# stepper_x2.net
KiCad netlist of a schematic drawn in EAGLE
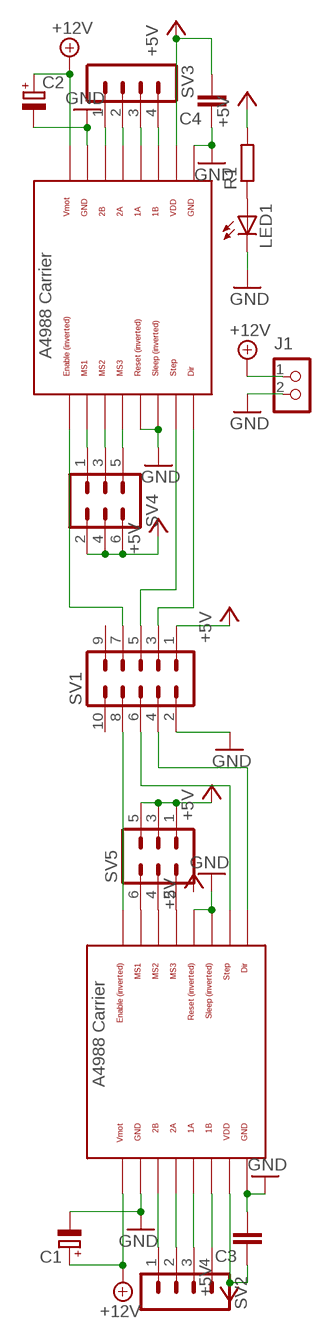
[diagram p0: schematic, sheet 1]

(export (version "E")
  (design (tool "Eeschema 10.0.6"))
  (components
    (comp (ref "C1")
      (value "CPOL-EU153CLV-0605")
      (footprint "eagle-import:153CLV-0605")
      (libsource (lib "eagle-import") (part "CPOL-EU153CLV-0605"))
    )
    (comp (ref "C2")
      (value "CPOL-EU153CLV-0605")
      (footprint "eagle-import:153CLV-0605")
      (libsource (lib "eagle-import") (part "CPOL-EU153CLV-0605"))
    )
    (comp (ref "C3")
      (value "C-EU025-030X050")
      (footprint "eagle-import:C025-030X050")
      (libsource (lib "eagle-import") (part "C-EU025-030X050"))
    )
    (comp (ref "C4")
      (value "C-EU025-030X050")
      (footprint "eagle-import:C025-030X050")
      (libsource (lib "eagle-import") (part "C-EU025-030X050"))
    )
    (comp (ref "J1")
      (value "CON_TERMINAL_BLOCK_02-5MM")
      (footprint "eagle-import:TERMINAL_BLOCK_2P_5")
      (libsource (lib "eagle-import") (part "CON_TERMINAL_BLOCK_02-5MM"))
    )
    (comp (ref "LED1")
      (value "LED5MM")
      (footprint "eagle-import:LED5MM")
      (libsource (lib "eagle-import") (part "LED5MM"))
    )
    (comp (ref "R1")
      (value "R-EU_0411/12")
      (footprint "eagle-import:0411_12")
      (libsource (lib "eagle-import") (part "R-EU_0411/12"))
    )
    (comp (ref "SV1")
      (value "MA05-2")
      (footprint "eagle-import:MA05-2")
      (libsource (lib "eagle-import") (part "MA05-2"))
    )
    (comp (ref "SV2")
      (value "MA04-1")
      (footprint "eagle-import:MA04-1")
      (libsource (lib "eagle-import") (part "MA04-1"))
    )
    (comp (ref "SV3")
      (value "MA04-1")
      (footprint "eagle-import:MA04-1")
      (libsource (lib "eagle-import") (part "MA04-1"))
    )
    (comp (ref "SV4")
      (value "MA03-2")
      (footprint "eagle-import:MA03-2")
      (libsource (lib "eagle-import") (part "MA03-2"))
    )
    (comp (ref "SV5")
      (value "MA03-2")
      (footprint "eagle-import:MA03-2")
      (libsource (lib "eagle-import") (part "MA03-2"))
    )
    (comp (ref "U$1")
      (value "POLOLU_A4983CARRIER")
      (footprint "eagle-import:A4988BREAKOUT")
      (libsource (lib "eagle-import") (part "POLOLU_A4983CARRIER"))
    )
    (comp (ref "U$2")
      (value "POLOLU_A4983CARRIER")
      (footprint "eagle-import:A4988BREAKOUT")
      (libsource (lib "eagle-import") (part "POLOLU_A4983CARRIER"))
    )
  )
  (nets
    (net (code "1") (name "+5V") (class "Default")
      (node (ref "C3") (pin "1") (pinfunction "1_1") (pintype "passive"))
      (node (ref "C4") (pin "2") (pinfunction "2_2") (pintype "passive"))
      (node (ref "R1") (pin "2") (pinfunction "2_2") (pintype "passive"))
      (node (ref "SV1") (pin "1") (pinfunction "1_1") (pintype "passive"))
      (node (ref "SV4") (pin "2") (pinfunction "2_2") (pintype "passive"))
      (node (ref "SV4") (pin "4") (pinfunction "4_4") (pintype "passive"))
      (node (ref "SV4") (pin "6") (pinfunction "6_6") (pintype "passive"))
      (node (ref "SV5") (pin "1") (pinfunction "1_1") (pintype "passive"))
      (node (ref "SV5") (pin "3") (pinfunction "3_3") (pintype "passive"))
      (node (ref "SV5") (pin "5") (pinfunction "5_5") (pintype "passive"))
      (node (ref "U$1") (pin "VDD") (pinfunction "VDD_VDD") (pintype "power_in"))
      (node (ref "U$2") (pin "VDD") (pinfunction "VDD_VDD") (pintype "power_in"))
    )
    (net (code "2") (name "+12V") (class "Default")
      (node (ref "C1") (pin "+") (pinfunction "+_+") (pintype "passive"))
      (node (ref "C2") (pin "+") (pinfunction "+_+") (pintype "passive"))
      (node (ref "J1") (pin "1") (pinfunction "1_1") (pintype "passive"))
      (node (ref "U$1") (pin "VMOT") (pinfunction "VMOT_VMOT") (pintype "power_in"))
      (node (ref "U$2") (pin "VMOT") (pinfunction "VMOT_VMOT") (pintype "power_in"))
    )
    (net (code "3") (name "GND") (class "Default")
      (node (ref "C1") (pin "-") (pinfunction "-_-") (pintype "passive"))
      (node (ref "C2") (pin "-") (pinfunction "-_-") (pintype "passive"))
      (node (ref "C3") (pin "2") (pinfunction "2_2") (pintype "passive"))
      (node (ref "C4") (pin "1") (pinfunction "1_1") (pintype "passive"))
      (node (ref "J1") (pin "2") (pinfunction "2_2") (pintype "passive"))
      (node (ref "LED1") (pin "K") (pinfunction "C_K") (pintype "passive"))
      (node (ref "SV1") (pin "2") (pinfunction "2_2") (pintype "passive"))
      (node (ref "U$1") (pin "GND") (pinfunction "GND_GND") (pintype "power_in"))
      (node (ref "U$1") (pin "GND@0") (pinfunction "GND_GND@0") (pintype "power_in"))
      (node (ref "U$1") (pin "RST") (pinfunction "RST_RST") (pintype "input"))
      (node (ref "U$1") (pin "SLP") (pinfunction "SLEEP_SLP") (pintype "input"))
      (node (ref "U$2") (pin "GND") (pinfunction "GND_GND") (pintype "power_in"))
      (node (ref "U$2") (pin "GND@0") (pinfunction "GND_GND@0") (pintype "power_in"))
      (node (ref "U$2") (pin "RST") (pinfunction "RST_RST") (pintype "input"))
      (node (ref "U$2") (pin "SLP") (pinfunction "SLEEP_SLP") (pintype "input"))
    )
    (net (code "4") (name "Net-(LED1-PadA)") (class "Default")
      (node (ref "LED1") (pin "A") (pinfunction "A_A") (pintype "passive"))
      (node (ref "R1") (pin "1") (pinfunction "1_1") (pintype "passive"))
    )
    (net (code "5") (name "Net-(SV1-Pad3)") (class "Default")
      (node (ref "SV1") (pin "3") (pinfunction "3_3") (pintype "passive"))
      (node (ref "U$1") (pin "DIR") (pinfunction "DIR_DIR") (pintype "input"))
    )
    (net (code "6") (name "Net-(SV1-Pad4)") (class "Default")
      (node (ref "SV1") (pin "4") (pinfunction "4_4") (pintype "passive"))
      (node (ref "U$2") (pin "DIR") (pinfunction "DIR_DIR") (pintype "input"))
    )
    (net (code "7") (name "Net-(SV1-Pad5)") (class "Default")
      (node (ref "SV1") (pin "5") (pinfunction "5_5") (pintype "passive"))
      (node (ref "U$1") (pin "STEP") (pinfunction "STEP_STEP") (pintype "input"))
    )
    (net (code "8") (name "Net-(SV1-Pad6)") (class "Default")
      (node (ref "SV1") (pin "6") (pinfunction "6_6") (pintype "passive"))
      (node (ref "U$2") (pin "STEP") (pinfunction "STEP_STEP") (pintype "input"))
    )
    (net (code "9") (name "Net-(SV1-Pad7)") (class "Default")
      (node (ref "SV1") (pin "7") (pinfunction "7_7") (pintype "passive"))
      (node (ref "U$1") (pin "EN") (pinfunction "EN_EN") (pintype "input"))
    )
    (net (code "10") (name "Net-(SV1-Pad8)") (class "Default")
      (node (ref "SV1") (pin "8") (pinfunction "8_8") (pintype "passive"))
      (node (ref "U$2") (pin "EN") (pinfunction "EN_EN") (pintype "input"))
    )
    (net (code "11") (name "Net-(SV2-Pad1)") (class "Default")
      (node (ref "SV2") (pin "1") (pinfunction "1_1") (pintype "passive"))
      (node (ref "U$2") (pin "2B") (pinfunction "2B_2B") (pintype "output"))
    )
    (net (code "12") (name "Net-(SV2-Pad2)") (class "Default")
      (node (ref "SV2") (pin "2") (pinfunction "2_2") (pintype "passive"))
      (node (ref "U$2") (pin "2A") (pinfunction "2A_2A") (pintype "output"))
    )
    (net (code "13") (name "Net-(SV2-Pad3)") (class "Default")
      (node (ref "SV2") (pin "3") (pinfunction "3_3") (pintype "passive"))
      (node (ref "U$2") (pin "1A") (pinfunction "1A_1A") (pintype "output"))
    )
    (net (code "14") (name "Net-(SV2-Pad4)") (class "Default")
      (node (ref "SV2") (pin "4") (pinfunction "4_4") (pintype "passive"))
      (node (ref "U$2") (pin "1B") (pinfunction "1B_1B") (pintype "output"))
    )
    (net (code "15") (name "Net-(SV3-Pad1)") (class "Default")
      (node (ref "SV3") (pin "1") (pinfunction "1_1") (pintype "passive"))
      (node (ref "U$1") (pin "2B") (pinfunction "2B_2B") (pintype "output"))
    )
    (net (code "16") (name "Net-(SV3-Pad2)") (class "Default")
      (node (ref "SV3") (pin "2") (pinfunction "2_2") (pintype "passive"))
      (node (ref "U$1") (pin "2A") (pinfunction "2A_2A") (pintype "output"))
    )
    (net (code "17") (name "Net-(SV3-Pad3)") (class "Default")
      (node (ref "SV3") (pin "3") (pinfunction "3_3") (pintype "passive"))
      (node (ref "U$1") (pin "1A") (pinfunction "1A_1A") (pintype "output"))
    )
    (net (code "18") (name "Net-(SV3-Pad4)") (class "Default")
      (node (ref "SV3") (pin "4") (pinfunction "4_4") (pintype "passive"))
      (node (ref "U$1") (pin "1B") (pinfunction "1B_1B") (pintype "output"))
    )
    (net (code "19") (name "Net-(SV4-Pad1)") (class "Default")
      (node (ref "SV4") (pin "1") (pinfunction "1_1") (pintype "passive"))
      (node (ref "U$1") (pin "MS1") (pinfunction "MS1_MS1") (pintype "input"))
    )
    (net (code "20") (name "Net-(SV4-Pad3)") (class "Default")
      (node (ref "SV4") (pin "3") (pinfunction "3_3") (pintype "passive"))
      (node (ref "U$1") (pin "MS2") (pinfunction "MS2_MS2") (pintype "input"))
    )
    (net (code "21") (name "Net-(SV4-Pad5)") (class "Default")
      (node (ref "SV4") (pin "5") (pinfunction "5_5") (pintype "passive"))
      (node (ref "U$1") (pin "MS3") (pinfunction "MS3_MS3") (pintype "input"))
    )
    (net (code "22") (name "Net-(SV5-Pad2)") (class "Default")
      (node (ref "SV5") (pin "2") (pinfunction "2_2") (pintype "passive"))
      (node (ref "U$2") (pin "MS3") (pinfunction "MS3_MS3") (pintype "input"))
    )
    (net (code "23") (name "Net-(SV5-Pad4)") (class "Default")
      (node (ref "SV5") (pin "4") (pinfunction "4_4") (pintype "passive"))
      (node (ref "U$2") (pin "MS2") (pinfunction "MS2_MS2") (pintype "input"))
    )
    (net (code "24") (name "Net-(SV5-Pad6)") (class "Default")
      (node (ref "SV5") (pin "6") (pinfunction "6_6") (pintype "passive"))
      (node (ref "U$2") (pin "MS1") (pinfunction "MS1_MS1") (pintype "input"))
    )
    (net (code "25") (name "unconnected-(SV1-Pad9)") (class "Default")
      (node (ref "SV1") (pin "9") (pinfunction "9_9") (pintype "passive"))
    )
    (net (code "26") (name "unconnected-(SV1-Pad10)") (class "Default")
      (node (ref "SV1") (pin "10") (pinfunction "10_10") (pintype "passive"))
    )
  )
)
